# Adapter_M2_B_M_to_E.net
KiCad netlist of a schematic drawn in Altium Designer
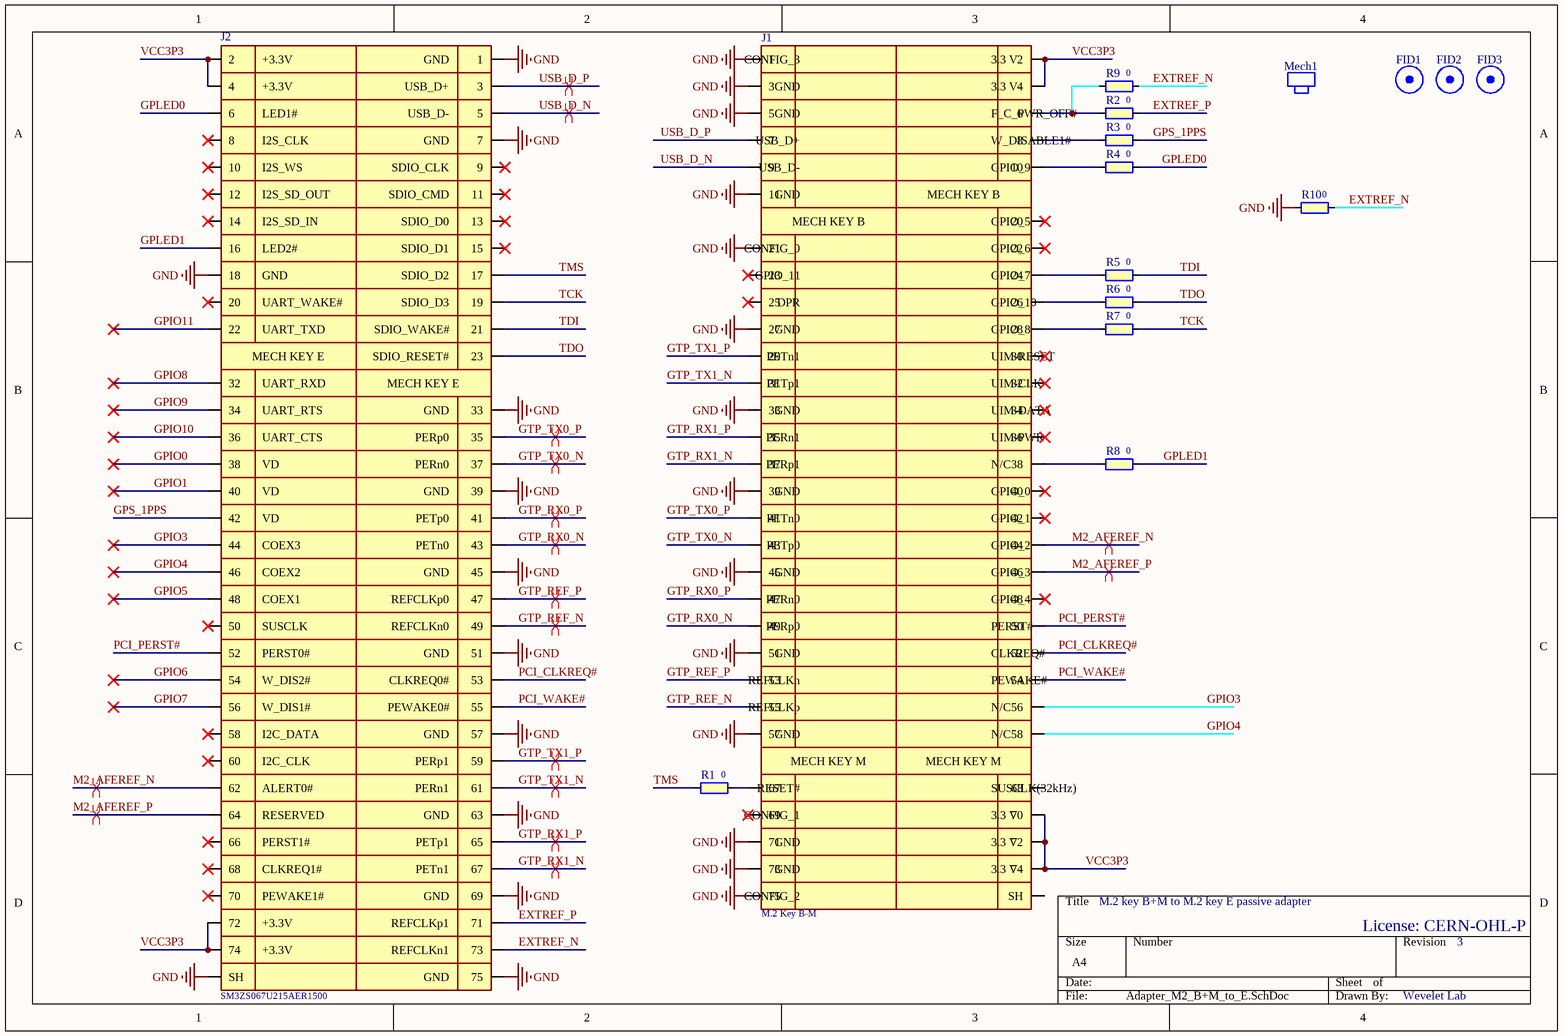
[diagram p0: Adapter_M2_B+M_to_E.SchDoc]

(export (version "E")
  (design (tool "Eeschema 10.0.6"))
  (components
    (comp (ref "FID1")
      (value "Fiducial")
      (footprint "Fiducial_2D")
      (libsource (lib "Mech") (part "Fiducial"))
    )
    (comp (ref "FID2")
      (value "Fiducial")
      (footprint "Fiducial_2D")
      (libsource (lib "Mech") (part "Fiducial"))
    )
    (comp (ref "FID3")
      (value "Fiducial")
      (footprint "Fiducial_2D")
      (libsource (lib "Mech") (part "Fiducial"))
    )
    (comp (ref "J1")
      (value "M.2 Key B-M")
      (footprint "EDGE_CONN_M.2_KEY_B-M")
      (description "Edge connector M.2, Key B-M")
      (fields (field (name "Comment") "Edge connector M.2 B-M"))
      (libsource (lib "Connectors") (part "Edge connector M.2 B-M"))
    )
    (comp (ref "J2")
      (value "SM3ZS067U215AER1500")
      (footprint "JAE_SM3ZS067U215AER1500")
      (description "Conn M.2, Key E, -40/+80, SMD")
      (fields (field (name "MANUFACTURER") "JAE"))
      (libsource (lib "Connectors") (part "SM3ZS067U215AER1500"))
    )
    (comp (ref "Mech1")
      (value "SM3ZS067U215-NUT1-R2500")
      (footprint "JAE_SM3ZS067U215-NUT1")
      (description "Mech, standoff, M2, 0.35 mm")
      (fields (field (name "MANUFACTURER") "JAE"))
      (libsource (lib "Mech") (part "SM3ZS067U215-NUT1-R2500"))
    )
    (comp (ref "R1")
      (value "0")
      (footprint "RESC60X30X35L15N")
      (description "Resistor, 0, 0.05W, 5%, 0201")
      (fields (field (name "Comment") "Res-0201-0-5%"))
      (libsource (lib "Resistors") (part "Res-0201-0-5%"))
    )
    (comp (ref "R2")
      (value "0")
      (footprint "RESC60X30X35L15N")
      (description "Resistor, 0, 0.05W, 5%, 0201")
      (fields (field (name "Comment") "Res-0201-0-5%"))
      (libsource (lib "Resistors") (part "Res-0201-0-5%"))
    )
    (comp (ref "R3")
      (value "0")
      (footprint "RESC60X30X35L15N")
      (description "Resistor, 0, 0.05W, 5%, 0201")
      (fields (field (name "Comment") "Res-0201-0-5%"))
      (libsource (lib "Resistors") (part "Res-0201-0-5%"))
    )
    (comp (ref "R4")
      (value "0")
      (footprint "RESC60X30X35L15N")
      (description "Resistor, 0, 0.05W, 5%, 0201")
      (fields (field (name "Comment") "Res-0201-0-5%"))
      (libsource (lib "Resistors") (part "Res-0201-0-5%"))
    )
    (comp (ref "R5")
      (value "0")
      (footprint "RESC60X30X35L15N")
      (description "Resistor, 0, 0.05W, 5%, 0201")
      (fields (field (name "Comment") "Res-0201-0-5%"))
      (libsource (lib "Resistors") (part "Res-0201-0-5%"))
    )
    (comp (ref "R6")
      (value "0")
      (footprint "RESC60X30X35L15N")
      (description "Resistor, 0, 0.05W, 5%, 0201")
      (fields (field (name "Comment") "Res-0201-0-5%"))
      (libsource (lib "Resistors") (part "Res-0201-0-5%"))
    )
    (comp (ref "R7")
      (value "0")
      (footprint "RESC60X30X35L15N")
      (description "Resistor, 0, 0.05W, 5%, 0201")
      (fields (field (name "Comment") "Res-0201-0-5%"))
      (libsource (lib "Resistors") (part "Res-0201-0-5%"))
    )
    (comp (ref "R8")
      (value "0")
      (footprint "RESC60X30X35L15N")
      (description "Resistor, 0, 0.05W, 5%, 0201")
      (fields (field (name "Comment") "Res-0201-0-5%"))
      (libsource (lib "Resistors") (part "Res-0201-0-5%"))
    )
    (comp (ref "R9")
      (value "0")
      (footprint "RESC60X30X35L15N")
      (description "Resistor, 0, 0.05W, 5%, 0201")
      (fields (field (name "Comment") "Res-0201-0-5%"))
      (libsource (lib "Resistors") (part "Res-0201-0-5%"))
    )
    (comp (ref "R10")
      (value "0")
      (footprint "RESC60X30X35L15N")
      (description "Resistor, 0, 0.05W, 5%, 0201")
      (fields (field (name "Comment") "Res-0201-0-5%"))
      (libsource (lib "Resistors") (part "Res-0201-0-5%"))
    )
  )
  (nets
    (net (code "1") (name "/EXTREF_N") (class "Default")
      (node (ref "J2") (pin "73") (pinfunction "73_73") (pintype "passive"))
      (node (ref "R10") (pin "2") (pinfunction "2_2") (pintype "passive"))
      (node (ref "R9") (pin "2") (pinfunction "2_2") (pintype "passive"))
    )
    (net (code "2") (name "/EXTREF_P") (class "Default")
      (node (ref "J2") (pin "71") (pinfunction "71_71") (pintype "passive"))
      (node (ref "R2") (pin "2") (pinfunction "2_2") (pintype "passive"))
    )
    (net (code "3") (name "/GPIO0") (class "Default")
      (node (ref "J2") (pin "38") (pinfunction "38_38") (pintype "passive+no_connect"))
    )
    (net (code "4") (name "/GPIO1") (class "Default")
      (node (ref "J2") (pin "40") (pinfunction "40_40") (pintype "passive+no_connect"))
    )
    (net (code "5") (name "/GPIO3") (class "Default")
      (node (ref "J1") (pin "56") (pinfunction "56_56") (pintype "passive"))
      (node (ref "J2") (pin "44") (pinfunction "44_44") (pintype "passive"))
    )
    (net (code "6") (name "/GPIO4") (class "Default")
      (node (ref "J1") (pin "58") (pinfunction "58_58") (pintype "passive"))
      (node (ref "J2") (pin "46") (pinfunction "46_46") (pintype "passive"))
    )
    (net (code "7") (name "/GPIO5") (class "Default")
      (node (ref "J2") (pin "48") (pinfunction "48_48") (pintype "passive+no_connect"))
    )
    (net (code "8") (name "/GPIO6") (class "Default")
      (node (ref "J2") (pin "54") (pinfunction "54_54") (pintype "passive+no_connect"))
    )
    (net (code "9") (name "/GPIO7") (class "Default")
      (node (ref "J2") (pin "56") (pinfunction "56_56") (pintype "passive+no_connect"))
    )
    (net (code "10") (name "/GPIO8") (class "Default")
      (node (ref "J2") (pin "32") (pinfunction "32_32") (pintype "passive+no_connect"))
    )
    (net (code "11") (name "/GPIO9") (class "Default")
      (node (ref "J2") (pin "34") (pinfunction "34_34") (pintype "passive+no_connect"))
    )
    (net (code "12") (name "/GPIO10") (class "Default")
      (node (ref "J2") (pin "36") (pinfunction "36_36") (pintype "passive+no_connect"))
    )
    (net (code "13") (name "/GPIO11") (class "Default")
      (node (ref "J2") (pin "22") (pinfunction "22_22") (pintype "passive+no_connect"))
    )
    (net (code "14") (name "/GPLED0") (class "Default")
      (node (ref "J2") (pin "6") (pinfunction "6_6") (pintype "passive"))
      (node (ref "R4") (pin "2") (pinfunction "2_2") (pintype "passive"))
    )
    (net (code "15") (name "/GPLED1") (class "Default")
      (node (ref "J2") (pin "16") (pinfunction "16_16") (pintype "passive"))
      (node (ref "R8") (pin "2") (pinfunction "2_2") (pintype "passive"))
    )
    (net (code "16") (name "/GPS_1PPS") (class "Default")
      (node (ref "J2") (pin "42") (pinfunction "42_42") (pintype "passive"))
      (node (ref "R3") (pin "2") (pinfunction "2_2") (pintype "passive"))
    )
    (net (code "17") (name "/GTP_REF_N") (class "Default")
      (node (ref "J1") (pin "55") (pinfunction "55_55") (pintype "passive"))
      (node (ref "J2") (pin "49") (pinfunction "49_49") (pintype "passive"))
    )
    (net (code "18") (name "/GTP_REF_P") (class "Default")
      (node (ref "J1") (pin "53") (pinfunction "53_53") (pintype "passive"))
      (node (ref "J2") (pin "47") (pinfunction "47_47") (pintype "passive"))
    )
    (net (code "19") (name "/GTP_RX0_N") (class "Default")
      (node (ref "J1") (pin "49") (pinfunction "49_49") (pintype "passive"))
      (node (ref "J2") (pin "43") (pinfunction "43_43") (pintype "passive"))
    )
    (net (code "20") (name "/GTP_RX0_P") (class "Default")
      (node (ref "J1") (pin "47") (pinfunction "47_47") (pintype "passive"))
      (node (ref "J2") (pin "41") (pinfunction "41_41") (pintype "passive"))
    )
    (net (code "21") (name "/GTP_RX1_N") (class "Default")
      (node (ref "J1") (pin "37") (pinfunction "37_37") (pintype "passive"))
      (node (ref "J2") (pin "67") (pinfunction "67_67") (pintype "passive"))
    )
    (net (code "22") (name "/GTP_RX1_P") (class "Default")
      (node (ref "J1") (pin "35") (pinfunction "35_35") (pintype "passive"))
      (node (ref "J2") (pin "65") (pinfunction "65_65") (pintype "passive"))
    )
    (net (code "23") (name "/GTP_TX0_N") (class "Default")
      (node (ref "J1") (pin "43") (pinfunction "43_43") (pintype "passive"))
      (node (ref "J2") (pin "37") (pinfunction "37_37") (pintype "passive"))
    )
    (net (code "24") (name "/GTP_TX0_P") (class "Default")
      (node (ref "J1") (pin "41") (pinfunction "41_41") (pintype "passive"))
      (node (ref "J2") (pin "35") (pinfunction "35_35") (pintype "passive"))
    )
    (net (code "25") (name "/GTP_TX1_N") (class "Default")
      (node (ref "J1") (pin "31") (pinfunction "31_31") (pintype "passive"))
      (node (ref "J2") (pin "61") (pinfunction "61_61") (pintype "passive"))
    )
    (net (code "26") (name "/GTP_TX1_P") (class "Default")
      (node (ref "J1") (pin "29") (pinfunction "29_29") (pintype "passive"))
      (node (ref "J2") (pin "59") (pinfunction "59_59") (pintype "passive"))
    )
    (net (code "27") (name "/M2_AFEREF_N") (class "Default")
      (node (ref "J1") (pin "44") (pinfunction "44_44") (pintype "passive"))
      (node (ref "J2") (pin "62") (pinfunction "62_62") (pintype "passive"))
    )
    (net (code "28") (name "/M2_AFEREF_P") (class "Default")
      (node (ref "J1") (pin "46") (pinfunction "46_46") (pintype "passive"))
      (node (ref "J2") (pin "64") (pinfunction "64_64") (pintype "passive"))
    )
    (net (code "29") (name "/PCI_CLKREQ#") (class "Default")
      (node (ref "J1") (pin "52") (pinfunction "52_52") (pintype "passive"))
      (node (ref "J2") (pin "53") (pinfunction "53_53") (pintype "passive"))
    )
    (net (code "30") (name "/PCI_PERST#") (class "Default")
      (node (ref "J1") (pin "50") (pinfunction "50_50") (pintype "passive"))
      (node (ref "J2") (pin "52") (pinfunction "52_52") (pintype "passive"))
    )
    (net (code "31") (name "/PCI_WAKE#") (class "Default")
      (node (ref "J1") (pin "54") (pinfunction "54_54") (pintype "passive"))
      (node (ref "J2") (pin "55") (pinfunction "55_55") (pintype "passive"))
    )
    (net (code "32") (name "/TCK") (class "Default")
      (node (ref "J2") (pin "19") (pinfunction "19_19") (pintype "passive"))
      (node (ref "R7") (pin "2") (pinfunction "2_2") (pintype "passive"))
    )
    (net (code "33") (name "/TDI") (class "Default")
      (node (ref "J2") (pin "21") (pinfunction "21_21") (pintype "passive"))
      (node (ref "R5") (pin "2") (pinfunction "2_2") (pintype "passive"))
    )
    (net (code "34") (name "/TDO") (class "Default")
      (node (ref "J2") (pin "23") (pinfunction "23_23") (pintype "passive"))
      (node (ref "R6") (pin "2") (pinfunction "2_2") (pintype "passive"))
    )
    (net (code "35") (name "/TMS") (class "Default")
      (node (ref "J2") (pin "17") (pinfunction "17_17") (pintype "passive"))
      (node (ref "R1") (pin "1") (pinfunction "1_1") (pintype "passive"))
    )
    (net (code "36") (name "/USB_D_N") (class "Default")
      (node (ref "J1") (pin "9") (pinfunction "9_9") (pintype "passive"))
      (node (ref "J2") (pin "5") (pinfunction "5_5") (pintype "passive"))
    )
    (net (code "37") (name "/USB_D_P") (class "Default")
      (node (ref "J1") (pin "7") (pinfunction "7_7") (pintype "passive"))
      (node (ref "J2") (pin "3") (pinfunction "3_3") (pintype "passive"))
    )
    (net (code "38") (name "/VCC3P3") (class "Default")
      (node (ref "J1") (pin "2") (pinfunction "2_2") (pintype "passive"))
      (node (ref "J1") (pin "4") (pinfunction "4_4") (pintype "passive"))
      (node (ref "J1") (pin "70") (pinfunction "70_70") (pintype "passive"))
      (node (ref "J1") (pin "72") (pinfunction "72_72") (pintype "passive"))
      (node (ref "J1") (pin "74") (pinfunction "74_74") (pintype "passive"))
      (node (ref "J2") (pin "2") (pinfunction "2_2") (pintype "passive"))
      (node (ref "J2") (pin "4") (pinfunction "4_4") (pintype "passive"))
      (node (ref "J2") (pin "72") (pinfunction "72_72") (pintype "passive"))
      (node (ref "J2") (pin "74") (pinfunction "74_74") (pintype "passive"))
    )
    (net (code "39") (name "GND") (class "Default")
      (node (ref "J1") (pin "1") (pinfunction "1_1") (pintype "passive"))
      (node (ref "J1") (pin "11") (pinfunction "11_11") (pintype "passive"))
      (node (ref "J1") (pin "21") (pinfunction "21_21") (pintype "passive"))
      (node (ref "J1") (pin "27") (pinfunction "27_27") (pintype "passive"))
      (node (ref "J1") (pin "3") (pinfunction "3_3") (pintype "passive"))
      (node (ref "J1") (pin "33") (pinfunction "33_33") (pintype "passive"))
      (node (ref "J1") (pin "39") (pinfunction "39_39") (pintype "passive"))
      (node (ref "J1") (pin "45") (pinfunction "45_45") (pintype "passive"))
      (node (ref "J1") (pin "5") (pinfunction "5_5") (pintype "passive"))
      (node (ref "J1") (pin "51") (pinfunction "51_51") (pintype "passive"))
      (node (ref "J1") (pin "57") (pinfunction "57_57") (pintype "passive"))
      (node (ref "J1") (pin "71") (pinfunction "71_71") (pintype "passive"))
      (node (ref "J1") (pin "73") (pinfunction "73_73") (pintype "passive"))
      (node (ref "J1") (pin "75") (pinfunction "75_75") (pintype "passive"))
      (node (ref "J2") (pin "1") (pinfunction "1_1") (pintype "passive"))
      (node (ref "J2") (pin "18") (pinfunction "18_18") (pintype "passive"))
      (node (ref "J2") (pin "33") (pinfunction "33_33") (pintype "passive"))
      (node (ref "J2") (pin "39") (pinfunction "39_39") (pintype "passive"))
      (node (ref "J2") (pin "45") (pinfunction "45_45") (pintype "passive"))
      (node (ref "J2") (pin "51") (pinfunction "51_51") (pintype "passive"))
      (node (ref "J2") (pin "57") (pinfunction "57_57") (pintype "passive"))
      (node (ref "J2") (pin "63") (pinfunction "63_63") (pintype "passive"))
      (node (ref "J2") (pin "69") (pinfunction "69_69") (pintype "passive"))
      (node (ref "J2") (pin "7") (pinfunction "7_7") (pintype "passive"))
      (node (ref "J2") (pin "75") (pinfunction "75_75") (pintype "passive"))
      (node (ref "J2") (pin "SH") (pinfunction "SH_SH") (pintype "passive"))
      (node (ref "R10") (pin "1") (pinfunction "1_1") (pintype "passive"))
    )
    (net (code "40") (name "Net-(J1-Pad6)") (class "Default")
      (node (ref "J1") (pin "6") (pinfunction "6_6") (pintype "passive"))
      (node (ref "R2") (pin "1") (pinfunction "1_1") (pintype "passive"))
      (node (ref "R9") (pin "1") (pinfunction "1_1") (pintype "passive"))
    )
    (net (code "41") (name "Net-(J1-Pad8)") (class "Default")
      (node (ref "J1") (pin "8") (pinfunction "8_8") (pintype "passive"))
      (node (ref "R3") (pin "1") (pinfunction "1_1") (pintype "passive"))
    )
    (net (code "42") (name "Net-(J1-Pad10)") (class "Default")
      (node (ref "J1") (pin "10") (pinfunction "10_10") (pintype "passive"))
      (node (ref "R4") (pin "1") (pinfunction "1_1") (pintype "passive"))
    )
    (net (code "43") (name "Net-(J1-Pad24)") (class "Default")
      (node (ref "J1") (pin "24") (pinfunction "24_24") (pintype "passive"))
      (node (ref "R5") (pin "1") (pinfunction "1_1") (pintype "passive"))
    )
    (net (code "44") (name "Net-(J1-Pad26)") (class "Default")
      (node (ref "J1") (pin "26") (pinfunction "26_26") (pintype "passive"))
      (node (ref "R6") (pin "1") (pinfunction "1_1") (pintype "passive"))
    )
    (net (code "45") (name "Net-(J1-Pad28)") (class "Default")
      (node (ref "J1") (pin "28") (pinfunction "28_28") (pintype "passive"))
      (node (ref "R7") (pin "1") (pinfunction "1_1") (pintype "passive"))
    )
    (net (code "46") (name "Net-(J1-Pad38)") (class "Default")
      (node (ref "J1") (pin "38") (pinfunction "38_38") (pintype "passive"))
      (node (ref "R8") (pin "1") (pinfunction "1_1") (pintype "passive"))
    )
    (net (code "47") (name "Net-(J1-Pad67)") (class "Default")
      (node (ref "J1") (pin "67") (pinfunction "67_67") (pintype "passive"))
      (node (ref "R1") (pin "2") (pinfunction "2_2") (pintype "passive"))
    )
    (net (code "48") (name "unconnected-(J1-Pad20)") (class "Default")
      (node (ref "J1") (pin "20") (pinfunction "20_20") (pintype "passive+no_connect"))
    )
    (net (code "49") (name "unconnected-(J1-Pad22)") (class "Default")
      (node (ref "J1") (pin "22") (pinfunction "22_22") (pintype "passive+no_connect"))
    )
    (net (code "50") (name "unconnected-(J1-Pad23)") (class "Default")
      (node (ref "J1") (pin "23") (pinfunction "23_23") (pintype "passive+no_connect"))
    )
    (net (code "51") (name "unconnected-(J1-Pad25)") (class "Default")
      (node (ref "J1") (pin "25") (pinfunction "25_25") (pintype "passive+no_connect"))
    )
    (net (code "52") (name "unconnected-(J1-Pad30)") (class "Default")
      (node (ref "J1") (pin "30") (pinfunction "30_30") (pintype "passive+no_connect"))
    )
    (net (code "53") (name "unconnected-(J1-Pad32)") (class "Default")
      (node (ref "J1") (pin "32") (pinfunction "32_32") (pintype "passive+no_connect"))
    )
    (net (code "54") (name "unconnected-(J1-Pad34)") (class "Default")
      (node (ref "J1") (pin "34") (pinfunction "34_34") (pintype "passive+no_connect"))
    )
    (net (code "55") (name "unconnected-(J1-Pad36)") (class "Default")
      (node (ref "J1") (pin "36") (pinfunction "36_36") (pintype "passive+no_connect"))
    )
    (net (code "56") (name "unconnected-(J1-Pad40)") (class "Default")
      (node (ref "J1") (pin "40") (pinfunction "40_40") (pintype "passive+no_connect"))
    )
    (net (code "57") (name "unconnected-(J1-Pad42)") (class "Default")
      (node (ref "J1") (pin "42") (pinfunction "42_42") (pintype "passive+no_connect"))
    )
    (net (code "58") (name "unconnected-(J1-Pad48)") (class "Default")
      (node (ref "J1") (pin "48") (pinfunction "48_48") (pintype "passive+no_connect"))
    )
    (net (code "59") (name "unconnected-(J1-Pad68)") (class "Default")
      (node (ref "J1") (pin "68") (pinfunction "68_68") (pintype "passive"))
    )
    (net (code "60") (name "unconnected-(J1-Pad69)") (class "Default")
      (node (ref "J1") (pin "69") (pinfunction "69_69") (pintype "passive+no_connect"))
    )
    (net (code "61") (name "unconnected-(J1-PadSH)") (class "Default")
      (node (ref "J1") (pin "SH") (pinfunction "SH_SH") (pintype "passive"))
    )
    (net (code "62") (name "unconnected-(J2-Pad8)") (class "Default")
      (node (ref "J2") (pin "8") (pinfunction "8_8") (pintype "passive+no_connect"))
    )
    (net (code "63") (name "unconnected-(J2-Pad9)") (class "Default")
      (node (ref "J2") (pin "9") (pinfunction "9_9") (pintype "passive+no_connect"))
    )
    (net (code "64") (name "unconnected-(J2-Pad10)") (class "Default")
      (node (ref "J2") (pin "10") (pinfunction "10_10") (pintype "passive+no_connect"))
    )
    (net (code "65") (name "unconnected-(J2-Pad11)") (class "Default")
      (node (ref "J2") (pin "11") (pinfunction "11_11") (pintype "passive+no_connect"))
    )
    (net (code "66") (name "unconnected-(J2-Pad12)") (class "Default")
      (node (ref "J2") (pin "12") (pinfunction "12_12") (pintype "passive+no_connect"))
    )
    (net (code "67") (name "unconnected-(J2-Pad13)") (class "Default")
      (node (ref "J2") (pin "13") (pinfunction "13_13") (pintype "passive+no_connect"))
    )
    (net (code "68") (name "unconnected-(J2-Pad14)") (class "Default")
      (node (ref "J2") (pin "14") (pinfunction "14_14") (pintype "passive+no_connect"))
    )
    (net (code "69") (name "unconnected-(J2-Pad15)") (class "Default")
      (node (ref "J2") (pin "15") (pinfunction "15_15") (pintype "passive+no_connect"))
    )
    (net (code "70") (name "unconnected-(J2-Pad20)") (class "Default")
      (node (ref "J2") (pin "20") (pinfunction "20_20") (pintype "passive+no_connect"))
    )
    (net (code "71") (name "unconnected-(J2-Pad50)") (class "Default")
      (node (ref "J2") (pin "50") (pinfunction "50_50") (pintype "passive+no_connect"))
    )
    (net (code "72") (name "unconnected-(J2-Pad58)") (class "Default")
      (node (ref "J2") (pin "58") (pinfunction "58_58") (pintype "passive+no_connect"))
    )
    (net (code "73") (name "unconnected-(J2-Pad60)") (class "Default")
      (node (ref "J2") (pin "60") (pinfunction "60_60") (pintype "passive+no_connect"))
    )
    (net (code "74") (name "unconnected-(J2-Pad66)") (class "Default")
      (node (ref "J2") (pin "66") (pinfunction "66_66") (pintype "passive+no_connect"))
    )
    (net (code "75") (name "unconnected-(J2-Pad68)") (class "Default")
      (node (ref "J2") (pin "68") (pinfunction "68_68") (pintype "passive+no_connect"))
    )
    (net (code "76") (name "unconnected-(J2-Pad70)") (class "Default")
      (node (ref "J2") (pin "70") (pinfunction "70_70") (pintype "passive+no_connect"))
    )
    (net (code "77") (name "unconnected-(Mech1-PadSH)") (class "Default")
      (node (ref "Mech1") (pin "SH") (pinfunction "SH_SH") (pintype "passive"))
    )
  )
)
